# Main.net
KiCad netlist of a schematic drawn in Altium Designer
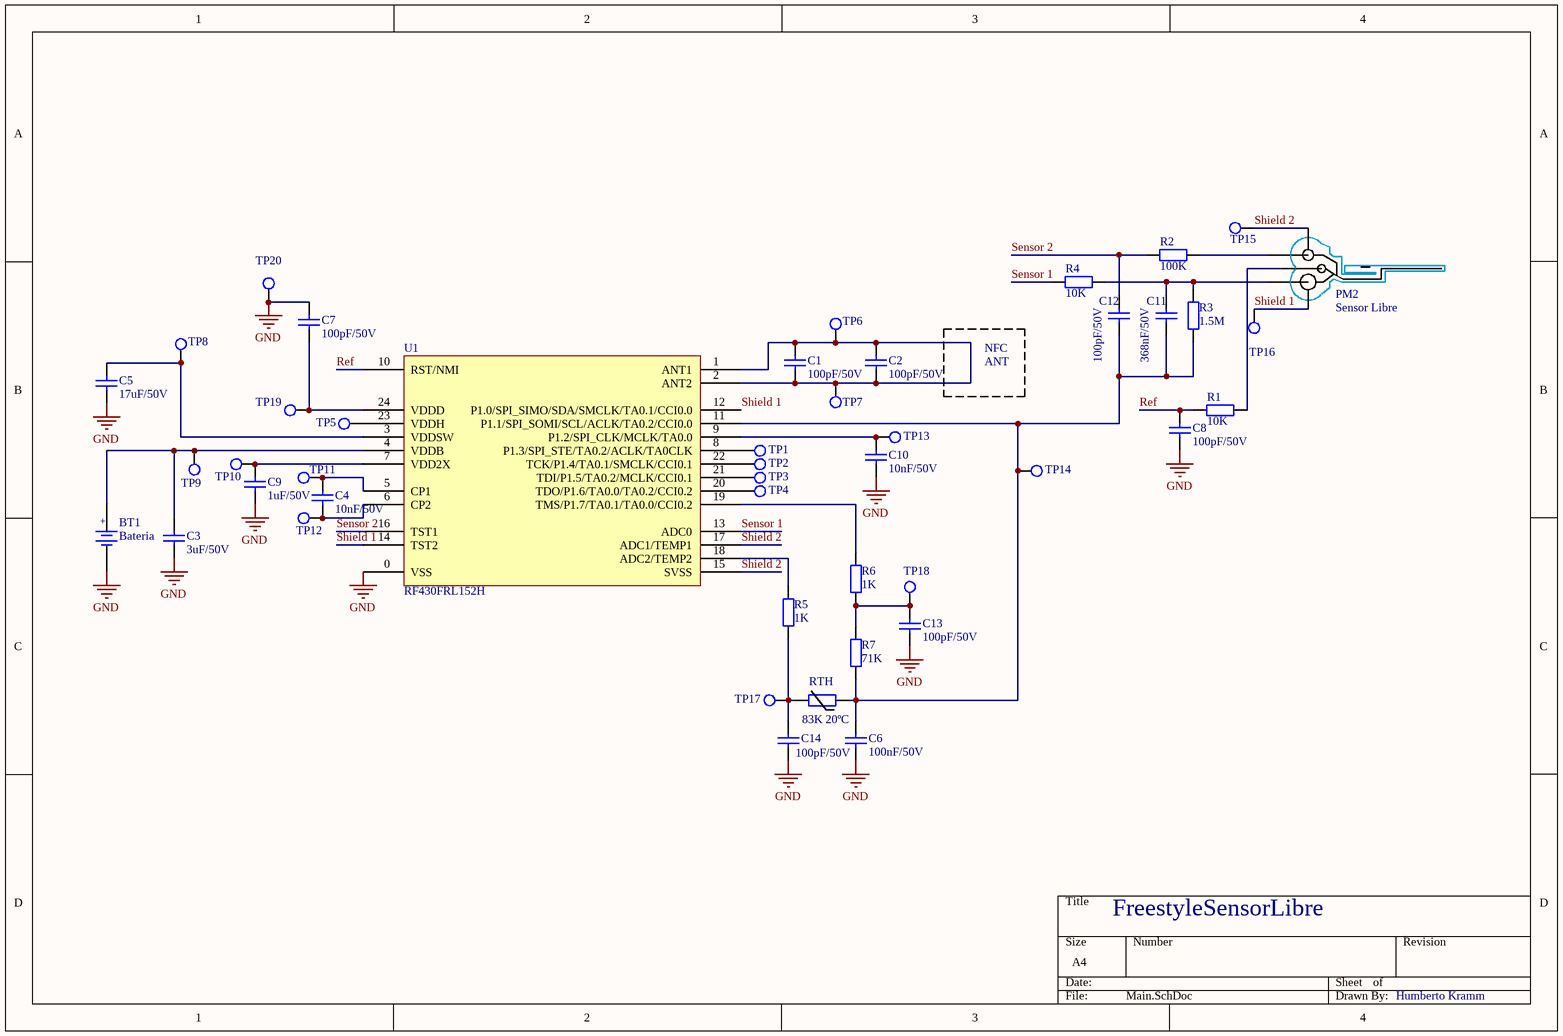
[diagram p0: Main.SchDoc]

(export (version "E")
  (design (tool "Eeschema 10.0.6"))
  (components
    (comp (ref "BT1")
      (value "Bateria")
      (footprint "BAT - V377")
      (description "Suporte para bateria")
      (fields (field (name "PUBLISHER") "Altium Limited"))
      (libsource (lib "almox Gaia") (part "Soquete Bat"))
    )
    (comp (ref "C1")
      (value "100pF/50V")
      (footprint "CAP 0402 - micro")
      (description "Capacitor Cerâmico")
      (fields (field (name "Comment") "Cap.Cer. 100pF/50V SMD") (field (name "PUBLISHER") "Altium Limited"))
      (libsource (lib "almox Gaia") (part "Cap.Cer. 150pF/50V SMD"))
    )
    (comp (ref "C2")
      (value "100pF/50V")
      (footprint "CAP 0402 - micro")
      (description "Capacitor Cerâmico")
      (fields (field (name "Comment") "Cap.Cer. 100pF/50V SMD") (field (name "PUBLISHER") "Altium Limited"))
      (libsource (lib "almox Gaia") (part "Cap.Cer. 150pF/50V SMD"))
    )
    (comp (ref "C3")
      (value "3uF/50V")
      (footprint "CAP 0603 - micro")
      (description "Capacitor Cerâmico")
      (fields (field (name "Comment") "Cap.Cer. 3uF/50V SMD") (field (name "PUBLISHER") "Altium Limited"))
      (libsource (lib "almox Gaia") (part "Cap.Cer. 1uF/50V SMD"))
    )
    (comp (ref "C4")
      (value "10nF/50V")
      (footprint "CAP 0402 - micro")
      (description "Capacitor Cerâmico")
      (fields (field (name "Comment") "Cap.Cer. 10nF/50V SMD") (field (name "PUBLISHER") "Altium Limited"))
      (libsource (lib "almox Gaia") (part "Cap.Cer. 10nF/50V SMD"))
    )
    (comp (ref "C5")
      (value "17uF/50V")
      (footprint "CAP 0603 - micro")
      (description "Capacitor Cerâmico")
      (fields (field (name "Comment") "Cap.Cer. 17uF/50V SMD") (field (name "PUBLISHER") "Altium Limited"))
      (libsource (lib "almox Gaia") (part "Cap.Cer. 1uF/50V SMD"))
    )
    (comp (ref "C6")
      (value "100nF/50V")
      (footprint "CAP 0402 - micro")
      (description "Capacitor Cerâmico")
      (fields (field (name "Comment") "Cap.Cer. 100nF/50V SMD") (field (name "PUBLISHER") "Altium Limited"))
      (libsource (lib "almox Gaia") (part "Cap.Cer. 100nF/50V SMD"))
    )
    (comp (ref "C7")
      (value "100pF/50V")
      (footprint "CAP 0402 - micro")
      (description "Capacitor Cerâmico")
      (fields (field (name "Comment") "Cap.Cer. 100pF/50V SMD") (field (name "PUBLISHER") "Altium Limited"))
      (libsource (lib "almox Gaia") (part "Cap.Cer. 150pF/50V SMD"))
    )
    (comp (ref "C8")
      (value "100pF/50V")
      (footprint "CAP 0402 - micro")
      (description "Capacitor Cerâmico")
      (fields (field (name "Comment") "Cap.Cer. 100pF/50V SMD") (field (name "PUBLISHER") "Altium Limited"))
      (libsource (lib "almox Gaia") (part "Cap.Cer. 150pF/50V SMD"))
    )
    (comp (ref "C9")
      (value "1uF/50V")
      (footprint "CAP 0402 - micro")
      (description "Capacitor Cerâmico")
      (fields (field (name "Comment") "Cap.Cer. 1uF/50V SMD") (field (name "PUBLISHER") "Altium Limited"))
      (libsource (lib "almox Gaia") (part "Cap.Cer. 1uF/50V SMD"))
    )
    (comp (ref "C10")
      (value "10nF/50V")
      (footprint "CAP 0201 - micro")
      (description "Capacitor Cerâmico")
      (fields (field (name "Comment") "Cap.Cer. 10nF/50V SMD") (field (name "PUBLISHER") "Altium Limited"))
      (libsource (lib "almox Gaia") (part "Cap.Cer. 10nF/50V SMD"))
    )
    (comp (ref "C11")
      (value "368nF/50V")
      (footprint "CAP 0603 - micro")
      (description "Capacitor Cerâmico")
      (fields (field (name "Comment") "Cap.Cer. 368nF/50V SMD") (field (name "PUBLISHER") "Altium Limited"))
      (libsource (lib "almox Gaia") (part "Cap.Cer. 100nF/50V SMD"))
    )
    (comp (ref "C12")
      (value "100pF/50V")
      (footprint "CAP 0603 - micro")
      (description "Capacitor Cerâmico")
      (fields (field (name "Comment") "Cap.Cer. 100pF/50V SMD") (field (name "PUBLISHER") "Altium Limited"))
      (libsource (lib "almox Gaia") (part "Cap.Cer. 150pF/50V SMD"))
    )
    (comp (ref "C13")
      (value "100pF/50V")
      (footprint "CAP 0402 - micro")
      (description "Capacitor Cerâmico")
      (fields (field (name "Comment") "Cap.Cer. 100pF/50V SMD") (field (name "PUBLISHER") "Altium Limited"))
      (libsource (lib "almox Gaia") (part "Cap.Cer. 150pF/50V SMD"))
    )
    (comp (ref "C14")
      (value "100pF/50V")
      (footprint "CAP 0402 - micro")
      (description "Capacitor Cerâmico")
      (fields (field (name "Comment") "Cap.Cer. 100pF/50V SMD") (field (name "PUBLISHER") "Altium Limited"))
      (libsource (lib "almox Gaia") (part "Cap.Cer. 150pF/50V SMD"))
    )
    (comp (ref "PM2")
      (value "Sensor Libre")
      (footprint "Libre_sensor")
      (fields (field (name "PUBLISHER") "Altium Limited"))
      (libsource (lib "almox Gaia") (part "Sensor Libre"))
    )
    (comp (ref "R1")
      (value "10K")
      (footprint "RES 0201 - micro")
      (description "Resistor")
      (fields (field (name "Comment") "Res 10K SMD") (field (name "PUBLISHER") "Altium Limited"))
      (libsource (lib "almox Gaia") (part "Res 10K SMD"))
    )
    (comp (ref "R2")
      (value "100K")
      (footprint "RES 0402 - micro")
      (description "Resistor")
      (fields (field (name "Comment") "Res 100K SMD") (field (name "PUBLISHER") "Altium Limited"))
      (libsource (lib "almox Gaia") (part "Res 100K SMD"))
    )
    (comp (ref "R3")
      (value "1.5M")
      (footprint "RES 0603 - micro")
      (description "Resistor")
      (fields (field (name "Comment") "Res 1.5M SMD") (field (name "PUBLISHER") "Altium Limited"))
      (libsource (lib "almox Gaia") (part "Res 2M SMD"))
    )
    (comp (ref "R4")
      (value "10K")
      (footprint "RES 0201 - micro")
      (description "Resistor")
      (fields (field (name "Comment") "Res 10K SMD") (field (name "PUBLISHER") "Altium Limited"))
      (libsource (lib "") (part "Res 10K SMD_1"))
    )
    (comp (ref "R5")
      (value "1K")
      (footprint "RES 0201 - micro")
      (description "Resistor")
      (fields (field (name "Comment") "Res 1K SMD") (field (name "PUBLISHER") "Altium Limited"))
      (libsource (lib "") (part "Res 1K SMD_1"))
    )
    (comp (ref "R6")
      (value "1K")
      (footprint "RES 0201 - micro")
      (description "Resistor")
      (fields (field (name "Comment") "Res 1K SMD") (field (name "PUBLISHER") "Altium Limited"))
      (libsource (lib "almox Gaia") (part "Res 1K SMD"))
    )
    (comp (ref "R7")
      (value "71K")
      (footprint "RES 0402 - micro")
      (description "Resistor")
      (fields (field (name "Comment") "Res 71K SMD") (field (name "PUBLISHER") "Altium Limited"))
      (libsource (lib "almox Gaia") (part "Res 68K SMD"))
    )
    (comp (ref "RTH")
      (value "83K 20ºC")
      (footprint "res 0805")
      (description "Thermistor")
      (fields (field (name "Comment") "Thermistor NTC") (field (name "PUBLISHER") "Altium Limited"))
      (libsource (lib "almox Gaia") (part "Thermistor NTC"))
    )
    (comp (ref "TP1")
      (value "Teste Point")
      (footprint "TestePoit_1mm")
      (fields (field (name "PUBLISHER") "Altium Limited"))
      (libsource (lib "almox Gaia") (part "Teste Point"))
    )
    (comp (ref "TP2")
      (value "Teste Point")
      (footprint "TestePoit_1mm")
      (fields (field (name "PUBLISHER") "Altium Limited"))
      (libsource (lib "almox Gaia") (part "Teste Point"))
    )
    (comp (ref "TP3")
      (value "Teste Point")
      (footprint "TestePoit_1mm")
      (fields (field (name "PUBLISHER") "Altium Limited"))
      (libsource (lib "almox Gaia") (part "Teste Point"))
    )
    (comp (ref "TP4")
      (value "Teste Point")
      (footprint "TestePoit_1mm")
      (fields (field (name "PUBLISHER") "Altium Limited"))
      (libsource (lib "almox Gaia") (part "Teste Point"))
    )
    (comp (ref "TP5")
      (value "Teste Point")
      (footprint "TestePoit_1mm")
      (fields (field (name "PUBLISHER") "Altium Limited"))
      (libsource (lib "almox Gaia") (part "Teste Point"))
    )
    (comp (ref "TP6")
      (value "Teste Point")
      (footprint "TestePoit_1mm")
      (fields (field (name "PUBLISHER") "Altium Limited"))
      (libsource (lib "almox Gaia") (part "Teste Point"))
    )
    (comp (ref "TP7")
      (value "Teste Point")
      (footprint "TestePoit_1mm")
      (fields (field (name "PUBLISHER") "Altium Limited"))
      (libsource (lib "almox Gaia") (part "Teste Point"))
    )
    (comp (ref "TP8")
      (value "Teste Point")
      (footprint "TestePoit_1mm")
      (fields (field (name "PUBLISHER") "Altium Limited"))
      (libsource (lib "almox Gaia") (part "Teste Point"))
    )
    (comp (ref "TP9")
      (value "Teste Point")
      (footprint "TestePoit_1mm")
      (fields (field (name "PUBLISHER") "Altium Limited"))
      (libsource (lib "almox Gaia") (part "Teste Point"))
    )
    (comp (ref "TP10")
      (value "Teste Point")
      (footprint "TestePoit_1mm")
      (fields (field (name "PUBLISHER") "Altium Limited"))
      (libsource (lib "almox Gaia") (part "Teste Point"))
    )
    (comp (ref "TP11")
      (value "Teste Point")
      (footprint "TestePoit_1mm")
      (fields (field (name "PUBLISHER") "Altium Limited"))
      (libsource (lib "almox Gaia") (part "Teste Point"))
    )
    (comp (ref "TP12")
      (value "Teste Point")
      (footprint "TestePoit_1mm")
      (fields (field (name "PUBLISHER") "Altium Limited"))
      (libsource (lib "almox Gaia") (part "Teste Point"))
    )
    (comp (ref "TP13")
      (value "Teste Point")
      (footprint "TestePoit_1mm")
      (fields (field (name "PUBLISHER") "Altium Limited"))
      (libsource (lib "almox Gaia") (part "Teste Point"))
    )
    (comp (ref "TP14")
      (value "Teste Point")
      (footprint "TestePoit_1mm")
      (fields (field (name "PUBLISHER") "Altium Limited"))
      (libsource (lib "almox Gaia") (part "Teste Point"))
    )
    (comp (ref "TP15")
      (value "Teste Point")
      (footprint "TestePoit_1mm")
      (fields (field (name "PUBLISHER") "Altium Limited"))
      (libsource (lib "almox Gaia") (part "Teste Point"))
    )
    (comp (ref "TP16")
      (value "Teste Point")
      (footprint "TestePoit_1mm")
      (fields (field (name "PUBLISHER") "Altium Limited"))
      (libsource (lib "almox Gaia") (part "Teste Point"))
    )
    (comp (ref "TP17")
      (value "Teste Point")
      (footprint "TestePoit_1mm")
      (fields (field (name "PUBLISHER") "Altium Limited"))
      (libsource (lib "almox Gaia") (part "Teste Point"))
    )
    (comp (ref "TP18")
      (value "Teste Point")
      (footprint "TestePoit_1mm")
      (fields (field (name "PUBLISHER") "Altium Limited"))
      (libsource (lib "almox Gaia") (part "Teste Point"))
    )
    (comp (ref "TP19")
      (value "Teste Point")
      (footprint "TestePoit_1mm")
      (fields (field (name "PUBLISHER") "Altium Limited"))
      (libsource (lib "almox Gaia") (part "Teste Point"))
    )
    (comp (ref "TP20")
      (value "Teste Point")
      (footprint "TestePoit_1mm")
      (fields (field (name "PUBLISHER") "Altium Limited"))
      (libsource (lib "almox Gaia") (part "Teste Point"))
    )
    (comp (ref "U1")
      (value "RF430FRL152H")
      (footprint "VQFN 24")
      (description "NFC ISO15693 Sensor Transponder With SPI/I2C Interface and 14-Bit Sigma-Delta ADC")
      (libsource (lib "almox Gaia") (part "RF430FRL152H"))
    )
  )
  (nets
    (net (code "1") (name "/Ref") (class "Default")
      (node (ref "C8") (pin "2") (pinfunction "2_2") (pintype "passive"))
      (node (ref "R1") (pin "1") (pinfunction "1_1") (pintype "passive"))
      (node (ref "U1") (pin "10") (pinfunction "RST/NMI_10") (pintype "passive"))
    )
    (net (code "2") (name "/Sensor 1") (class "Default")
      (node (ref "R4") (pin "2") (pinfunction "2_2") (pintype "passive"))
      (node (ref "U1") (pin "13") (pinfunction "ADC0_13") (pintype "passive"))
    )
    (net (code "3") (name "/Sensor 2") (class "Default")
      (node (ref "C12") (pin "1") (pinfunction "1_1") (pintype "passive"))
      (node (ref "R2") (pin "1") (pinfunction "1_1") (pintype "passive"))
      (node (ref "U1") (pin "16") (pinfunction "TST1_16") (pintype "passive"))
    )
    (net (code "4") (name "/Shield 1") (class "Default")
      (node (ref "PM2") (pin "4") (pinfunction "4_4") (pintype "passive"))
      (node (ref "TP16") (pin "1") (pinfunction "A_1") (pintype "passive"))
      (node (ref "U1") (pin "12") (pinfunction "P1.0/SPI_SIMO/SDA/SMCLK/TA0.1/CCI0.0_12") (pintype "passive"))
      (node (ref "U1") (pin "14") (pinfunction "TST2_14") (pintype "passive"))
    )
    (net (code "5") (name "/Shield 2") (class "Default")
      (node (ref "PM2") (pin "5") (pinfunction "5_5") (pintype "passive"))
      (node (ref "TP15") (pin "1") (pinfunction "A_1") (pintype "passive"))
      (node (ref "U1") (pin "15") (pinfunction "SVSS_15") (pintype "passive"))
      (node (ref "U1") (pin "17") (pinfunction "ADC1/TEMP1_17") (pintype "passive"))
    )
    (net (code "6") (name "GND") (class "Default")
      (node (ref "BT1") (pin "2") (pinfunction "-_2") (pintype "passive"))
      (node (ref "C10") (pin "1") (pinfunction "1_1") (pintype "passive"))
      (node (ref "C13") (pin "2") (pinfunction "2_2") (pintype "passive"))
      (node (ref "C14") (pin "2") (pinfunction "2_2") (pintype "passive"))
      (node (ref "C3") (pin "1") (pinfunction "1_1") (pintype "passive"))
      (node (ref "C5") (pin "1") (pinfunction "1_1") (pintype "passive"))
      (node (ref "C6") (pin "2") (pinfunction "2_2") (pintype "passive"))
      (node (ref "C7") (pin "2") (pinfunction "2_2") (pintype "passive"))
      (node (ref "C8") (pin "1") (pinfunction "1_1") (pintype "passive"))
      (node (ref "C9") (pin "1") (pinfunction "1_1") (pintype "passive"))
      (node (ref "TP20") (pin "1") (pinfunction "A_1") (pintype "passive"))
      (node (ref "U1") (pin "0") (pinfunction "VSS_0") (pintype "passive"))
    )
    (net (code "7") (name "Net-(BT1-+)") (class "Default")
      (node (ref "BT1") (pin "1") (pinfunction "+_1") (pintype "passive"))
      (node (ref "C3") (pin "2") (pinfunction "2_2") (pintype "passive"))
      (node (ref "TP9") (pin "1") (pinfunction "A_1") (pintype "passive"))
      (node (ref "U1") (pin "4") (pinfunction "VDDB_4") (pintype "passive"))
    )
    (net (code "8") (name "Net-(C11-Pad1)") (class "Default")
      (node (ref "C11") (pin "1") (pinfunction "1_1") (pintype "passive"))
      (node (ref "PM2") (pin "2") (pinfunction "2_2") (pintype "passive"))
      (node (ref "R3") (pin "1") (pinfunction "1_1") (pintype "passive"))
      (node (ref "R4") (pin "1") (pinfunction "1_1") (pintype "passive"))
    )
    (net (code "9") (name "Net-(PM2-Pad1)") (class "Default")
      (node (ref "PM2") (pin "1") (pinfunction "1_1") (pintype "passive"))
      (node (ref "R1") (pin "2") (pinfunction "2_2") (pintype "passive"))
    )
    (net (code "10") (name "Net-(PM2-Pad3)") (class "Default")
      (node (ref "PM2") (pin "3") (pinfunction "3_3") (pintype "passive"))
      (node (ref "R2") (pin "2") (pinfunction "2_2") (pintype "passive"))
    )
    (net (code "11") (name "Net-(TP1-A)") (class "Default")
      (node (ref "TP1") (pin "1") (pinfunction "A_1") (pintype "passive"))
      (node (ref "U1") (pin "8") (pinfunction "P1.3/SPI_STE/TA0.2/ACLK/TA0CLK_8") (pintype "passive"))
    )
    (net (code "12") (name "Net-(TP2-A)") (class "Default")
      (node (ref "TP2") (pin "1") (pinfunction "A_1") (pintype "passive"))
      (node (ref "U1") (pin "22") (pinfunction "TCK/P1.4/TA0.1/SMCLK/CCI0.1_22") (pintype "passive"))
    )
    (net (code "13") (name "Net-(TP3-A)") (class "Default")
      (node (ref "TP3") (pin "1") (pinfunction "A_1") (pintype "passive"))
      (node (ref "U1") (pin "21") (pinfunction "TDI/P1.5/TA0.2/MCLK/CCI0.1_21") (pintype "passive"))
    )
    (net (code "14") (name "Net-(TP4-A)") (class "Default")
      (node (ref "TP4") (pin "1") (pinfunction "A_1") (pintype "passive"))
      (node (ref "U1") (pin "20") (pinfunction "TDO/P1.6/TA0.0/TA0.2/CCI0.2_20") (pintype "passive"))
    )
    (net (code "15") (name "Net-(TP5-A)") (class "Default")
      (node (ref "TP5") (pin "1") (pinfunction "A_1") (pintype "passive"))
      (node (ref "U1") (pin "23") (pinfunction "VDDH_23") (pintype "passive"))
    )
    (net (code "16") (name "Net-(TP6-A)") (class "Default")
      (node (ref "C1") (pin "1") (pinfunction "1_1") (pintype "passive"))
      (node (ref "C1") (pin "2") (pinfunction "2_2") (pintype "passive"))
      (node (ref "C2") (pin "1") (pinfunction "1_1") (pintype "passive"))
      (node (ref "C2") (pin "2") (pinfunction "2_2") (pintype "passive"))
      (node (ref "TP6") (pin "1") (pinfunction "A_1") (pintype "passive"))
      (node (ref "TP7") (pin "1") (pinfunction "A_1") (pintype "passive"))
      (node (ref "U1") (pin "1") (pinfunction "ANT1_1") (pintype "passive"))
      (node (ref "U1") (pin "2") (pinfunction "ANT2_2") (pintype "passive"))
    )
    (net (code "17") (name "Net-(TP8-A)") (class "Default")
      (node (ref "C5") (pin "2") (pinfunction "2_2") (pintype "passive"))
      (node (ref "TP8") (pin "1") (pinfunction "A_1") (pintype "passive"))
      (node (ref "U1") (pin "3") (pinfunction "VDDSW_3") (pintype "passive"))
    )
    (net (code "18") (name "Net-(TP10-A)") (class "Default")
      (node (ref "C9") (pin "2") (pinfunction "2_2") (pintype "passive"))
      (node (ref "TP10") (pin "1") (pinfunction "A_1") (pintype "passive"))
      (node (ref "U1") (pin "7") (pinfunction "VDD2X_7") (pintype "passive"))
    )
    (net (code "19") (name "Net-(TP11-A)") (class "Default")
      (node (ref "C4") (pin "2") (pinfunction "2_2") (pintype "passive"))
      (node (ref "TP11") (pin "1") (pinfunction "A_1") (pintype "passive"))
      (node (ref "U1") (pin "5") (pinfunction "CP1_5") (pintype "passive"))
    )
    (net (code "20") (name "Net-(TP12-A)") (class "Default")
      (node (ref "C4") (pin "1") (pinfunction "1_1") (pintype "passive"))
      (node (ref "TP12") (pin "1") (pinfunction "A_1") (pintype "passive"))
      (node (ref "U1") (pin "6") (pinfunction "CP2_6") (pintype "passive"))
    )
    (net (code "21") (name "Net-(TP13-A)") (class "Default")
      (node (ref "C10") (pin "2") (pinfunction "2_2") (pintype "passive"))
      (node (ref "TP13") (pin "1") (pinfunction "A_1") (pintype "passive"))
      (node (ref "U1") (pin "9") (pinfunction "P1.2/SPI_CLK/MCLK/TA0.0_9") (pintype "passive"))
    )
    (net (code "22") (name "Net-(TP14-A)") (class "Default")
      (node (ref "C11") (pin "2") (pinfunction "2_2") (pintype "passive"))
      (node (ref "C12") (pin "2") (pinfunction "2_2") (pintype "passive"))
      (node (ref "C6") (pin "1") (pinfunction "1_1") (pintype "passive"))
      (node (ref "R3") (pin "2") (pinfunction "2_2") (pintype "passive"))
      (node (ref "R7") (pin "1") (pinfunction "1_1") (pintype "passive"))
      (node (ref "RTH") (pin "1") (pinfunction "1_1") (pintype "passive"))
      (node (ref "TP14") (pin "1") (pinfunction "A_1") (pintype "passive"))
      (node (ref "U1") (pin "11") (pinfunction "P1.1/SPI_SOMI/SCL/ACLK/TA0.2/CCI0.0_11") (pintype "passive"))
    )
    (net (code "23") (name "Net-(TP17-A)") (class "Default")
      (node (ref "C14") (pin "1") (pinfunction "1_1") (pintype "passive"))
      (node (ref "R5") (pin "2") (pinfunction "2_2") (pintype "passive"))
      (node (ref "RTH") (pin "2") (pinfunction "2_2") (pintype "passive"))
      (node (ref "TP17") (pin "1") (pinfunction "A_1") (pintype "passive"))
    )
    (net (code "24") (name "Net-(TP18-A)") (class "Default")
      (node (ref "C13") (pin "1") (pinfunction "1_1") (pintype "passive"))
      (node (ref "R6") (pin "1") (pinfunction "1_1") (pintype "passive"))
      (node (ref "R7") (pin "2") (pinfunction "2_2") (pintype "passive"))
      (node (ref "TP18") (pin "1") (pinfunction "A_1") (pintype "passive"))
    )
    (net (code "25") (name "Net-(TP19-A)") (class "Default")
      (node (ref "C7") (pin "1") (pinfunction "1_1") (pintype "passive"))
      (node (ref "TP19") (pin "1") (pinfunction "A_1") (pintype "passive"))
      (node (ref "U1") (pin "24") (pinfunction "VDDD_24") (pintype "passive"))
    )
    (net (code "26") (name "Net-(U1-ADC2{slash}TEMP2)") (class "Default")
      (node (ref "R5") (pin "1") (pinfunction "1_1") (pintype "passive"))
      (node (ref "U1") (pin "18") (pinfunction "ADC2/TEMP2_18") (pintype "passive"))
    )
    (net (code "27") (name "Net-(U1-TMS{slash}P1.7{slash}TA0.1{slash}TA0.0{slash}CCI0.2)") (class "Default")
      (node (ref "R6") (pin "2") (pinfunction "2_2") (pintype "passive"))
      (node (ref "U1") (pin "19") (pinfunction "TMS/P1.7/TA0.1/TA0.0/CCI0.2_19") (pintype "passive"))
    )
  )
)
